# Power_Schematic.net
KiCad netlist of a schematic drawn in Altium Designer
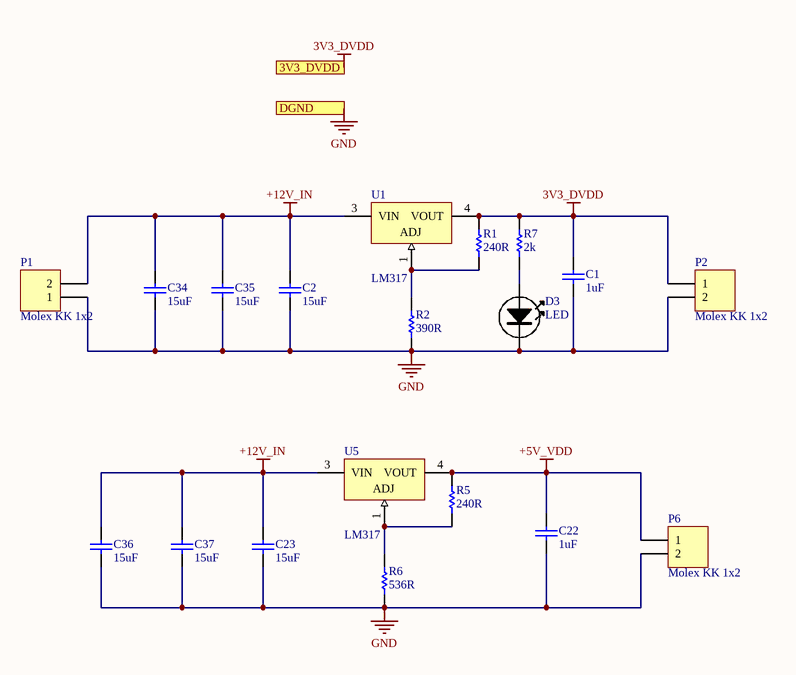
[diagram p0: Power_Schematic.SchDoc]

(export (version "E")
  (design (tool "Eeschema 10.0.6"))
  (components
    (comp (ref "C1")
      (value "1uF")
      (footprint "C0805")
      (description "0805 Capacitor")
      (libsource (lib "PARSEC") (part "C0805"))
    )
    (comp (ref "C2")
      (value "15uF")
      (footprint "C0805")
      (description "0805 Capacitor")
      (libsource (lib "PARSEC") (part "C0805"))
    )
    (comp (ref "C22")
      (value "1uF")
      (footprint "C0805")
      (description "0805 Capacitor")
      (libsource (lib "PARSEC") (part "C0805"))
    )
    (comp (ref "C23")
      (value "15uF")
      (footprint "C0805")
      (description "0805 Capacitor")
      (libsource (lib "PARSEC") (part "C0805"))
    )
    (comp (ref "C34")
      (value "15uF")
      (footprint "C0805")
      (description "0805 Capacitor")
      (libsource (lib "PARSEC") (part "C0805"))
    )
    (comp (ref "C35")
      (value "15uF")
      (footprint "C0805")
      (description "0805 Capacitor")
      (libsource (lib "PARSEC") (part "C0805"))
    )
    (comp (ref "C36")
      (value "15uF")
      (footprint "C0805")
      (description "0805 Capacitor")
      (libsource (lib "PARSEC") (part "C0805"))
    )
    (comp (ref "C37")
      (value "15uF")
      (footprint "C0805")
      (description "0805 Capacitor")
      (libsource (lib "PARSEC") (part "C0805"))
    )
    (comp (ref "D3")
      (value "LED")
      (footprint "0805LED")
      (fields
        (field (name "MANUFACTURER") "OSRAM Opto Semiconductors Inc")
        (field (name "MANUFACTURER PART NUMBER") "LS T676-Q1R2-1-Z")
      )
      (libsource (lib "PARSEC") (part "LED"))
    )
    (comp (ref "P1")
      (value "Molex KK 1x2")
      (footprint "Molex KK 2x1")
      (description "1x2 Molex KK Connector")
      (libsource (lib "") (part "Molex KK 1x2_1"))
    )
    (comp (ref "P2")
      (value "Molex KK 1x2")
      (footprint "Molex KK 2x1")
      (description "1x2 Molex KK Connector")
      (libsource (lib "PARSEC") (part "Molex KK 1x2"))
    )
    (comp (ref "P6")
      (value "Molex KK 1x2")
      (footprint "Molex KK 2x1")
      (description "1x2 Molex KK Connector")
      (libsource (lib "PARSEC") (part "Molex KK 1x2"))
    )
    (comp (ref "R1")
      (value "240R")
      (footprint "R0805")
      (description "RESISTOR 0805")
      (libsource (lib "PARSEC") (part "R0805"))
    )
    (comp (ref "R2")
      (value "390R")
      (footprint "R0805")
      (description "RESISTOR 0805")
      (libsource (lib "PARSEC") (part "R0805"))
    )
    (comp (ref "R5")
      (value "240R")
      (footprint "R0805")
      (description "RESISTOR 0805")
      (libsource (lib "PARSEC") (part "R0805"))
    )
    (comp (ref "R6")
      (value "536R")
      (footprint "R0805")
      (description "RESISTOR 0805")
      (libsource (lib "PARSEC") (part "R0805"))
    )
    (comp (ref "R7")
      (value "2k")
      (footprint "R0805")
      (description "RESISTOR 0805")
      (libsource (lib "PARSEC") (part "R0805"))
    )
    (comp (ref "U1")
      (value "LM317")
      (footprint "D-PAK")
      (description "Linear Voltage Regulator")
      (libsource (lib "PARSEC") (part "LM317"))
    )
    (comp (ref "U5")
      (value "LM317")
      (footprint "D-PAK")
      (description "Linear Voltage Regulator")
      (libsource (lib "PARSEC") (part "LM317"))
    )
  )
  (nets
    (net (code "1") (name "+5V_VDD") (class "Default")
      (node (ref "C22") (pin "1") (pinfunction "1_1") (pintype "passive"))
      (node (ref "P6") (pin "1") (pinfunction "1_1") (pintype "passive"))
      (node (ref "R5") (pin "2") (pinfunction "2_2") (pintype "passive"))
      (node (ref "U5") (pin "4") (pinfunction "VOUT_4") (pintype "power_in"))
    )
    (net (code "2") (name "+12V_IN") (class "Default")
      (node (ref "C2") (pin "1") (pinfunction "1_1") (pintype "passive"))
      (node (ref "C23") (pin "1") (pinfunction "1_1") (pintype "passive"))
      (node (ref "C34") (pin "1") (pinfunction "1_1") (pintype "passive"))
      (node (ref "C35") (pin "1") (pinfunction "1_1") (pintype "passive"))
      (node (ref "C36") (pin "1") (pinfunction "1_1") (pintype "passive"))
      (node (ref "C37") (pin "1") (pinfunction "1_1") (pintype "passive"))
      (node (ref "P1") (pin "2") (pinfunction "2_2") (pintype "passive"))
      (node (ref "U1") (pin "3") (pinfunction "VIN_3") (pintype "power_in"))
      (node (ref "U5") (pin "3") (pinfunction "VIN_3") (pintype "power_in"))
    )
    (net (code "3") (name "3V3_DVDD") (class "Default")
      (node (ref "C1") (pin "1") (pinfunction "1_1") (pintype "passive"))
      (node (ref "P2") (pin "1") (pinfunction "1_1") (pintype "passive"))
      (node (ref "R1") (pin "2") (pinfunction "2_2") (pintype "passive"))
      (node (ref "R7") (pin "2") (pinfunction "2_2") (pintype "passive"))
      (node (ref "U1") (pin "4") (pinfunction "VOUT_4") (pintype "power_in"))
    )
    (net (code "4") (name "GND") (class "Default")
      (node (ref "C1") (pin "2") (pinfunction "2_2") (pintype "passive"))
      (node (ref "C2") (pin "2") (pinfunction "2_2") (pintype "passive"))
      (node (ref "C22") (pin "2") (pinfunction "2_2") (pintype "passive"))
      (node (ref "C23") (pin "2") (pinfunction "2_2") (pintype "passive"))
      (node (ref "C34") (pin "2") (pinfunction "2_2") (pintype "passive"))
      (node (ref "C35") (pin "2") (pinfunction "2_2") (pintype "passive"))
      (node (ref "C36") (pin "2") (pinfunction "2_2") (pintype "passive"))
      (node (ref "C37") (pin "2") (pinfunction "2_2") (pintype "passive"))
      (node (ref "D3") (pin "K") (pintype "passive"))
      (node (ref "P1") (pin "1") (pinfunction "1_1") (pintype "passive"))
      (node (ref "P2") (pin "2") (pinfunction "2_2") (pintype "passive"))
      (node (ref "P6") (pin "2") (pinfunction "2_2") (pintype "passive"))
      (node (ref "R2") (pin "1") (pinfunction "1_1") (pintype "passive"))
      (node (ref "R6") (pin "1") (pinfunction "1_1") (pintype "passive"))
    )
    (net (code "5") (name "Net-(D3-PadA)") (class "Default")
      (node (ref "D3") (pin "A") (pintype "passive"))
      (node (ref "R7") (pin "1") (pinfunction "1_1") (pintype "passive"))
    )
    (net (code "6") (name "Net-(U1-ADJ)") (class "Default")
      (node (ref "R1") (pin "1") (pinfunction "1_1") (pintype "passive"))
      (node (ref "R2") (pin "2") (pinfunction "2_2") (pintype "passive"))
      (node (ref "U1") (pin "1") (pinfunction "ADJ_1") (pintype "input"))
    )
    (net (code "7") (name "Net-(U5-ADJ)") (class "Default")
      (node (ref "R5") (pin "1") (pinfunction "1_1") (pintype "passive"))
      (node (ref "R6") (pin "2") (pinfunction "2_2") (pintype "passive"))
      (node (ref "U5") (pin "1") (pinfunction "ADJ_1") (pintype "input"))
    )
  )
)
